# PERIPHERALS.net
KiCad netlist of a schematic drawn in Altium Designer
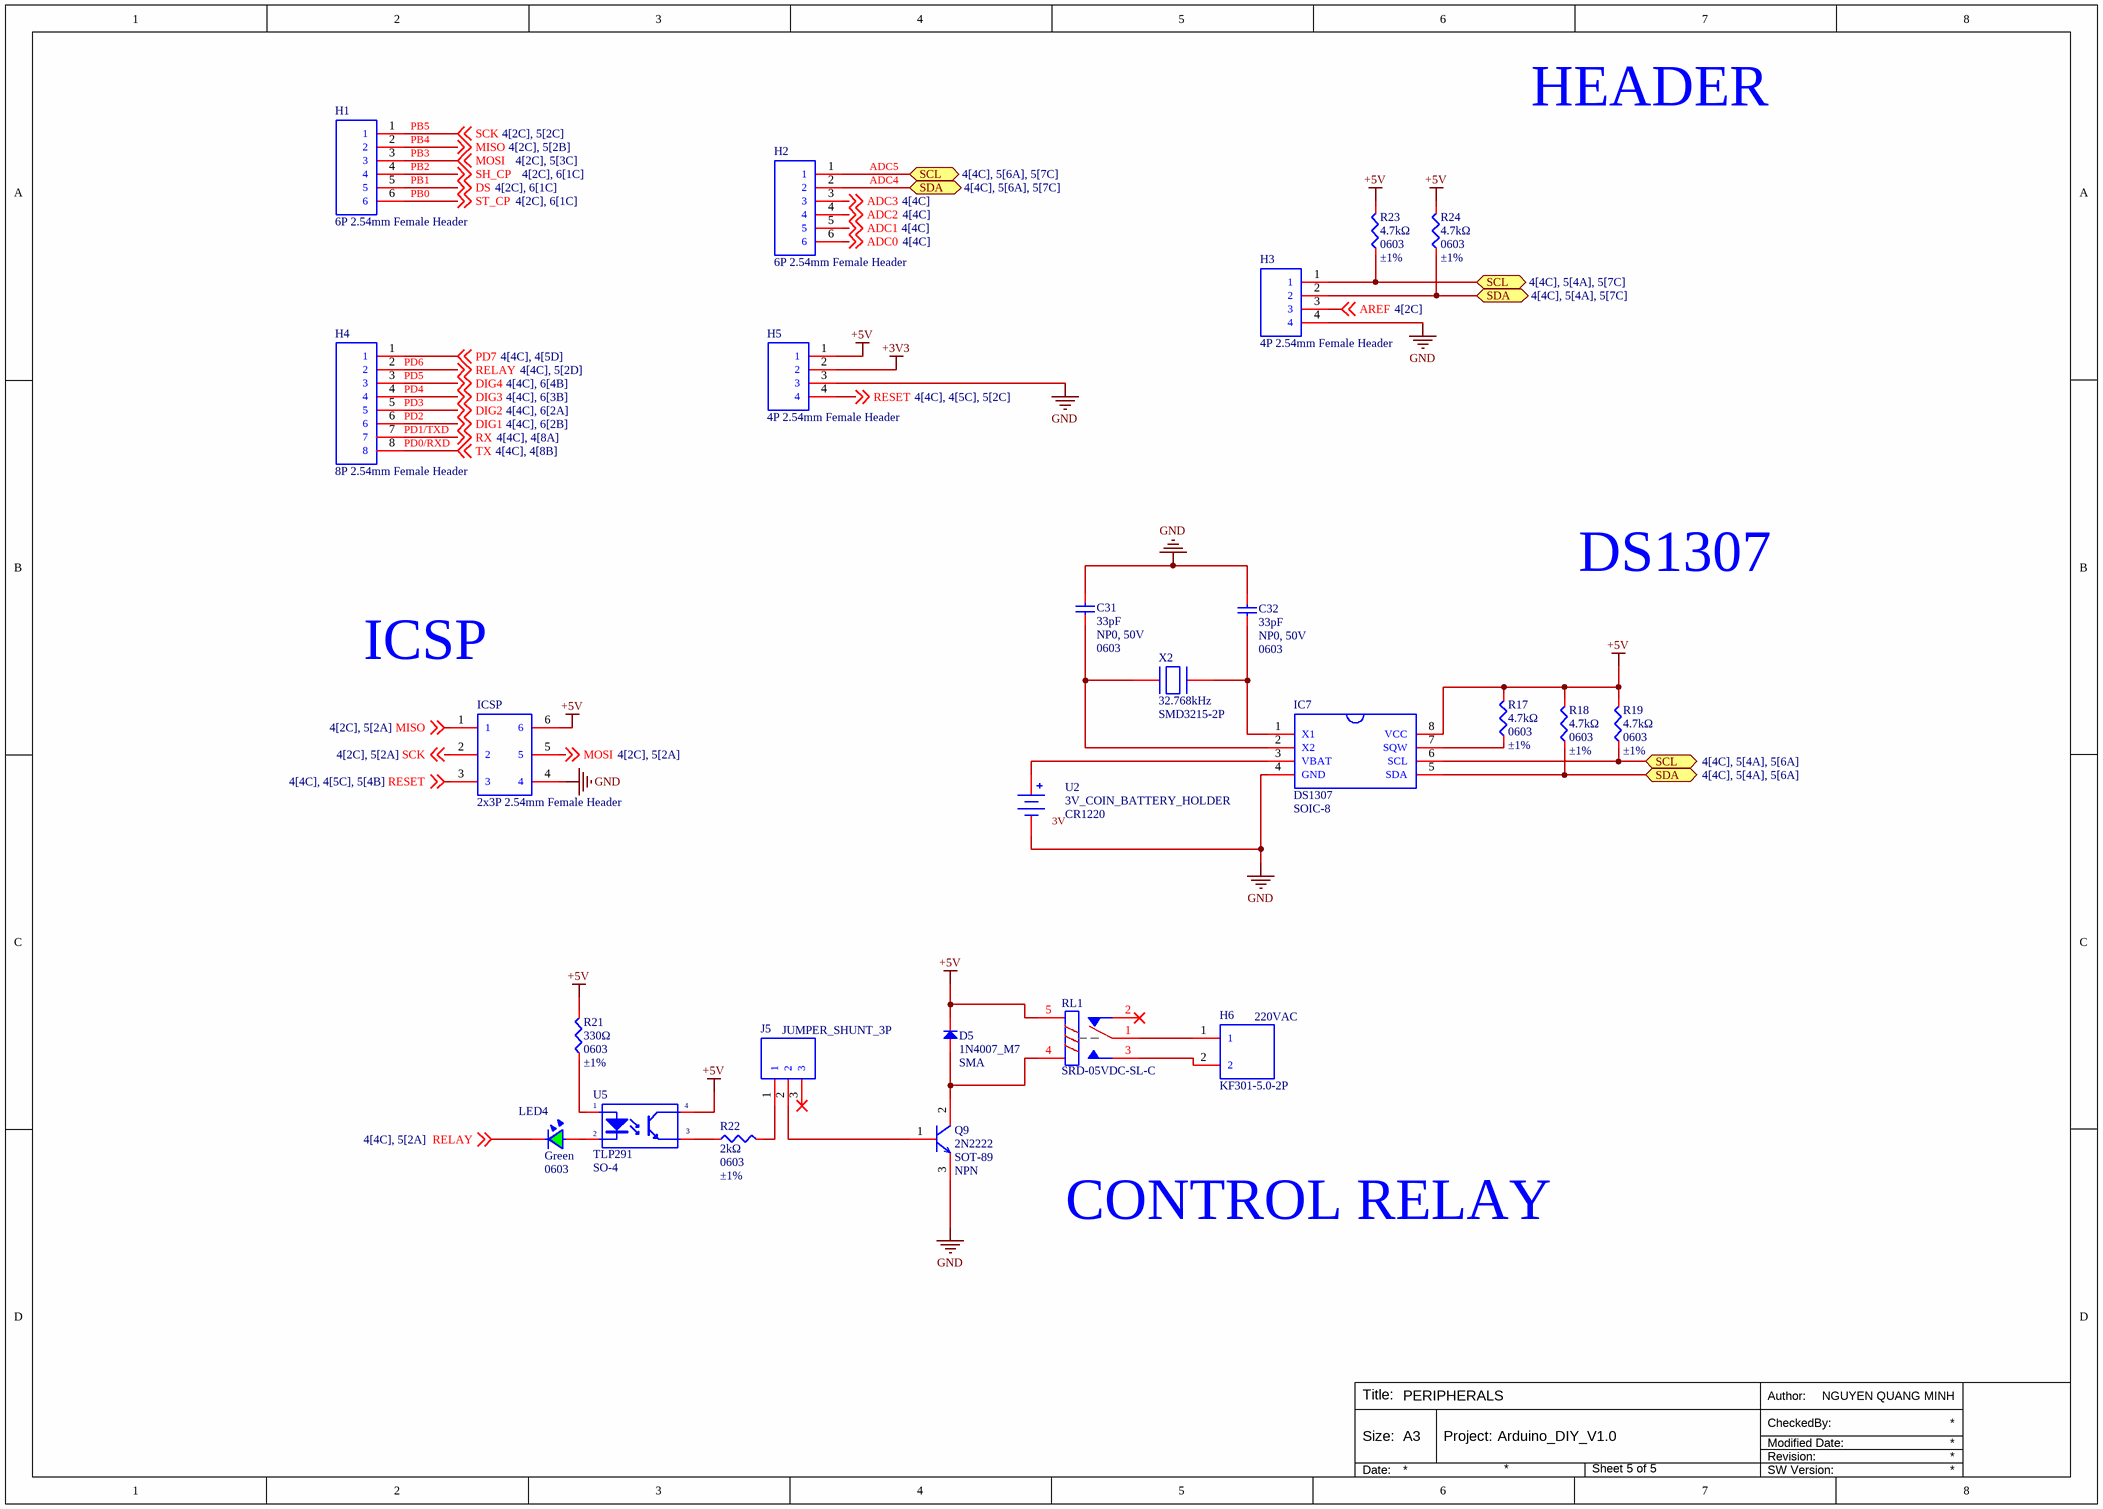
[diagram p0: PERIPHERALS.SchDoc]

(export (version "E")
  (design (tool "Eeschema 10.0.6"))
  (components
    (comp (ref "C31")
      (value "33pF")
      (footprint "C0603")
      (description "50V 33pF NP0 ±5% 0603 Multilayer Ceramic Capacitors MLCC - SMD/SMT ROHS")
      (fields
        (field (name "MANUFACTURER") "YAGEO")
        (field (name "MFR. PART") "CC0603JRNPO9BN330")
        (field (name "TEMPERATURE COEFFICIENT") "NP0, 50V")
        (field (name "PACKAGE") "0603")
      )
      (libsource (lib "Capacitor") (part "C0603_MLCC_33pF_NP0_50V"))
    )
    (comp (ref "C32")
      (value "33pF")
      (footprint "C0603")
      (description "50V 33pF NP0 ±5% 0603 Multilayer Ceramic Capacitors MLCC - SMD/SMT ROHS")
      (fields
        (field (name "MANUFACTURER") "YAGEO")
        (field (name "MFR. PART") "CC0603JRNPO9BN330")
        (field (name "TEMPERATURE COEFFICIENT") "NP0, 50V")
        (field (name "PACKAGE") "0603")
      )
      (libsource (lib "Capacitor") (part "C0603_MLCC_33pF_NP0_50V"))
    )
    (comp (ref "D5")
      (value "1N4007_M7")
      (footprint "SMA(DO-214AC)")
      (description "1A 1V@1A 1kV SMA Diodes - General Purpose ROHS")
      (fields
        (field (name "MANUFACTURER") "JSMSEMI")
        (field (name "MFR. PART") "1N4007 M7")
        (field (name "PACKAGE") "SMA")
      )
      (libsource (lib "DIODE") (part "1N4007_M7"))
    )
    (comp (ref "H1")
      (value "6P 2.54mm Female Header")
      (footprint "6P, 2,54mm, FEMALE HEADER")
      (description "2.54mm 1 6P Through Hole 1x6P Through Hole,P=2.54mm Female Headers ROHS")
      (fields
        (field (name "MANUFACTURER") "BOOMELE(Boom Precision Elec)")
        (field (name "MFR. PART") "2.54-1*6P")
      )
      (libsource (lib "HEADER") (part "6P 2.54mm Female Header"))
    )
    (comp (ref "H2")
      (value "6P 2.54mm Female Header")
      (footprint "6P, 2,54mm, FEMALE HEADER")
      (description "2.54mm 1 6P Through Hole 1x6P Through Hole,P=2.54mm Female Headers ROHS")
      (fields
        (field (name "MANUFACTURER") "BOOMELE(Boom Precision Elec)")
        (field (name "MFR. PART") "2.54-1*6P")
      )
      (libsource (lib "HEADER") (part "6P 2.54mm Female Header"))
    )
    (comp (ref "H3")
      (value "4P 2.54mm Female Header")
      (footprint "4P, 2,54mm, FEMALE HEADER")
      (fields
        (field (name "MANUFACTURER") "BOOMELE(Boom Precision Elec)")
        (field (name "MFR. PART") "2.54-1*4P")
        (field (name "LCSC PART") "C2718488")
      )
      (libsource (lib "HEADER") (part "4P 2.54mm Female Header"))
    )
    (comp (ref "H4")
      (value "8P 2.54mm Female Header")
      (footprint "8P, 2,54mm, FEMALE HEADER")
      (description "2.54mm 1 8P Through Hole 1x8P Through Hole,P=2.54mm Female Headers ROHS")
      (fields
        (field (name "MANUFACTURER") "BOOMELE(Boom Precision Elec)")
        (field (name "MFR. PART") "2.54-1*8P")
      )
      (libsource (lib "HEADER") (part "8P 2.54mm Female Header"))
    )
    (comp (ref "H5")
      (value "4P 2.54mm Female Header")
      (footprint "4P, 2,54mm, FEMALE HEADER")
      (fields
        (field (name "MANUFACTURER") "BOOMELE(Boom Precision Elec)")
        (field (name "MFR. PART") "2.54-1*4P")
        (field (name "LCSC PART") "C2718488")
      )
      (libsource (lib "HEADER") (part "4P 2.54mm Female Header"))
    )
    (comp (ref "H6")
      (value "KF301-5.0-2P")
      (footprint "CONN-TH_P5.00_KF301-5.0-2P")
      (fields
        (field (name "MANUFACTURER") "Cixi Kefa Elec")
        (field (name "LCSC PART") "C474881")
        (field (name "CONFIGURE") "220VAC")
      )
      (libsource (lib "CONNECTER") (part "KF301-5.0-2P"))
    )
    (comp (ref "IC7")
      (value "DS1307")
      (footprint "SOIC-8")
      (description "I2C SOIC-8 Real Time Clocks ROHS")
      (fields
        (field (name "MANUFACTURER") "MAXIM")
        (field (name "MFR. PART") "DS1307Z+T&R")
        (field (name "PACKAGE") "SOIC-8")
      )
      (libsource (lib "IC") (part "DS1307-SOIC8"))
    )
    (comp (ref "ICSP")
      (value "2x3P 2.54mm Female Header")
      (footprint "2x3P, 2.54mm, Female Header")
      (fields
        (field (name "MANUFACTURER") "HanElectricity")
        (field (name "MFR. PART") "2541FV-2x3P")
        (field (name "LCSC PART") "C18723054")
      )
      (libsource (lib "HEADER") (part "2x3P 2.54mm Female Header"))
    )
    (comp (ref "J5")
      (value "JUMPER_SHUNT_3P")
      (footprint "JUMPER_SHUNT_3P")
      (fields
        (field (name "MANUFACTURER") "XFCN")
        (field (name "MFR. PART") "PZ254V-11-03P")
        (field (name "LCSC PART") "C2937625")
      )
      (libsource (lib "JUMP") (part "JUMPER_SHUNT_3P"))
    )
    (comp (ref "LED4")
      (value "Green")
      (footprint "LED0603_GREEN")
      (fields
        (field (name "MANUFACTURER") "Kingbright")
        (field (name "MFR. PART") "KPT-1608LVZGCK")
        (field (name "LCSC PART") "C598356")
        (field (name "PACKAGE") "0603")
      )
      (libsource (lib "LED") (part "LED0603_Green"))
    )
    (comp (ref "Q9")
      (value "2N2222")
      (footprint "SOT-89-3L")
      (description "40V 500mW 600mA NPN SOT-89 Bipolar (BJT) ROHS")
      (fields
        (field (name "MANUFACTURER") "CBI")
        (field (name "MFR. PART") "2N2222AU")
        (field (name "PACKAGE") "SOT-89")
        (field (name "TYPE") "NPN")
      )
      (libsource (lib "BJT and FET") (part "2N2222_SOT-89"))
    )
    (comp (ref "R17")
      (value "4.7kΩ")
      (footprint "R0603")
      (description "100mW Thick Film Resistor 75V ±100ppm/℃ ±1% 4.7kΩ 0603 Chip Resistor - Surface Mount ROHS")
      (fields
        (field (name "MANUFACTURER") "YAGEO")
        (field (name "MFR. PART") "RC0603FR-074K7L")
        (field (name "PACKAGE") "0603")
        (field (name "TOLERANCE") "±1%")
      )
      (libsource (lib "Resistor") (part "R0603_4.7kΩ_±1%"))
    )
    (comp (ref "R18")
      (value "4.7kΩ")
      (footprint "R0603")
      (description "100mW Thick Film Resistor 75V ±100ppm/℃ ±1% 4.7kΩ 0603 Chip Resistor - Surface Mount ROHS")
      (fields
        (field (name "MANUFACTURER") "YAGEO")
        (field (name "MFR. PART") "RC0603FR-074K7L")
        (field (name "PACKAGE") "0603")
        (field (name "TOLERANCE") "±1%")
      )
      (libsource (lib "Resistor") (part "R0603_4.7kΩ_±1%"))
    )
    (comp (ref "R19")
      (value "4.7kΩ")
      (footprint "R0603")
      (description "100mW Thick Film Resistor 75V ±100ppm/℃ ±1% 4.7kΩ 0603 Chip Resistor - Surface Mount ROHS")
      (fields
        (field (name "MANUFACTURER") "YAGEO")
        (field (name "MFR. PART") "RC0603FR-074K7L")
        (field (name "PACKAGE") "0603")
        (field (name "TOLERANCE") "±1%")
      )
      (libsource (lib "Resistor") (part "R0603_4.7kΩ_±1%"))
    )
    (comp (ref "R21")
      (value "330Ω")
      (footprint "R0603")
      (description "100mW Thick Film Resistor 75V ±100ppm/℃ ±1% 330Ω 0603 Chip Resistor - Surface Mount ROHS")
      (fields
        (field (name "MANUFACTURER") "YAGEO")
        (field (name "MFR. PART") "RC0603FR-07330RL")
        (field (name "PACKAGE") "0603")
        (field (name "TOLERANCE") "±1%")
      )
      (libsource (lib "Resistor") (part "R0603_330Ω_±1%"))
    )
    (comp (ref "R22")
      (value "2kΩ")
      (footprint "R0603")
      (description "100mW Thick Film Resistor 75V ±100ppm/℃ ±1% 2kΩ 0603 Chip Resistor - Surface Mount ROHS")
      (fields
        (field (name "MANUFACTURER") "YAGEO")
        (field (name "MFR. PART") "RC0603FR-072KL")
        (field (name "PACKAGE") "0603")
        (field (name "TOLERANCE") "±1%")
      )
      (libsource (lib "Resistor") (part "R0603_2kΩ_±1%"))
    )
    (comp (ref "R23")
      (value "4.7kΩ")
      (footprint "R0603")
      (description "100mW Thick Film Resistor 75V ±100ppm/℃ ±1% 4.7kΩ 0603 Chip Resistor - Surface Mount ROHS")
      (fields
        (field (name "MANUFACTURER") "YAGEO")
        (field (name "MFR. PART") "RC0603FR-074K7L")
        (field (name "PACKAGE") "0603")
        (field (name "TOLERANCE") "±1%")
      )
      (libsource (lib "Resistor") (part "R0603_4.7kΩ_±1%"))
    )
    (comp (ref "R24")
      (value "4.7kΩ")
      (footprint "R0603")
      (description "100mW Thick Film Resistor 75V ±100ppm/℃ ±1% 4.7kΩ 0603 Chip Resistor - Surface Mount ROHS")
      (fields
        (field (name "MANUFACTURER") "YAGEO")
        (field (name "MFR. PART") "RC0603FR-074K7L")
        (field (name "PACKAGE") "0603")
        (field (name "TOLERANCE") "±1%")
      )
      (libsource (lib "Resistor") (part "R0603_4.7kΩ_±1%"))
    )
    (comp (ref "RL1")
      (value "SRD-05VDC-SL-C")
      (footprint "Through Hole,15.6x19.2mm")
      (description "250V@AC 5V 15A 1 Form C: 1C (SPDT-CO) Through Hole,15.6x19.2mm Power Relays ROHS")
      (fields (field (name "MANUFACTURER") "Songle Relay") (field (name "LCSC PART") "C35449"))
      (libsource (lib "RELAY") (part "SRD-05VDC-SL-C"))
    )
    (comp (ref "U2")
      (value "3V_COIN_BATTERY_HOLDER")
      (footprint "3V_COIN_BATERRY_HOLDER_CR1220")
      (description "Battery Holder -25℃~+85℃ Phosphor Bronze CR1220 SMD Button And Strip Battery Connector ROHS")
      (fields
        (field (name "MANUFACTURER") "MYOUNG")
        (field (name "LCSC PART") "C964723")
        (field (name "BATTERY TYPE") "CR1220")
      )
      (libsource (lib "PIN") (part "3V_COIN_BATTERY_HOLDER"))
    )
    (comp (ref "U5")
      (value "TLP291")
      (footprint "SO-4")
      (description "SO-4 Transistor, Photovoltaic Output Optoisolators ROHS")
      (fields
        (field (name "MANUFACTURER") "TOSHIBA")
        (field (name "MFR. PART") "TLP291(GB-TP,SE(T")
        (field (name "PACKAGE") "SO-4")
      )
      (libsource (lib "OPTO") (part "TLP291"))
    )
    (comp (ref "X2")
      (value "32.768kHz")
      (footprint "SMD3215-2P")
      (description "32.768kHz 12.5pF ±20ppm SMD3215-2P Crystals ROHS")
      (fields
        (field (name "MANUFACTURER") "NDK")
        (field (name "MFR. PART") "NX3215SA-32.768K-STD-MUA-8")
        (field (name "PACKAGE") "SMD3215-2P")
      )
      (libsource (lib "CRYSTAL") (part "Crystal_32.768Khz"))
    )
  )
  (nets
    (net (code "1") (name "+3V3") (class "Default")
      (node (ref "H5") (pin "2") (pinfunction "2_2") (pintype "passive"))
    )
    (net (code "2") (name "+5V") (class "Default")
      (node (ref "D5") (pin "1") (pinfunction "1_1") (pintype "passive"))
      (node (ref "H5") (pin "1") (pinfunction "1_1") (pintype "passive"))
      (node (ref "IC7") (pin "8") (pinfunction "VCC_8") (pintype "passive"))
      (node (ref "ICSP") (pin "6") (pinfunction "6_6") (pintype "passive"))
      (node (ref "R17") (pin "2") (pinfunction "2_2") (pintype "passive"))
      (node (ref "R18") (pin "2") (pinfunction "2_2") (pintype "passive"))
      (node (ref "R19") (pin "2") (pinfunction "2_2") (pintype "passive"))
      (node (ref "R21") (pin "2") (pinfunction "2_2") (pintype "passive"))
      (node (ref "R23") (pin "2") (pinfunction "2_2") (pintype "passive"))
      (node (ref "R24") (pin "2") (pinfunction "2_2") (pintype "passive"))
      (node (ref "RL1") (pin "5") (pinfunction "5_5") (pintype "passive"))
      (node (ref "U5") (pin "4") (pinfunction "C_4") (pintype "passive"))
    )
    (net (code "3") (name "/SCL") (class "Default")
      (node (ref "H2") (pin "1") (pinfunction "1_1") (pintype "passive"))
      (node (ref "H3") (pin "1") (pinfunction "1_1") (pintype "passive"))
      (node (ref "IC7") (pin "6") (pinfunction "SCL_6") (pintype "passive"))
      (node (ref "R19") (pin "1") (pinfunction "1_1") (pintype "passive"))
      (node (ref "R23") (pin "1") (pinfunction "1_1") (pintype "passive"))
    )
    (net (code "4") (name "/SDA") (class "Default")
      (node (ref "H2") (pin "2") (pinfunction "2_2") (pintype "passive"))
      (node (ref "H3") (pin "2") (pinfunction "2_2") (pintype "passive"))
      (node (ref "IC7") (pin "5") (pinfunction "SDA_5") (pintype "passive"))
      (node (ref "R18") (pin "1") (pinfunction "1_1") (pintype "passive"))
      (node (ref "R24") (pin "1") (pinfunction "1_1") (pintype "passive"))
    )
    (net (code "5") (name "ADC0") (class "Default")
      (node (ref "H2") (pin "6") (pinfunction "6_6") (pintype "passive"))
    )
    (net (code "6") (name "ADC1") (class "Default")
      (node (ref "H2") (pin "5") (pinfunction "5_5") (pintype "passive"))
    )
    (net (code "7") (name "ADC2") (class "Default")
      (node (ref "H2") (pin "4") (pinfunction "4_4") (pintype "passive"))
    )
    (net (code "8") (name "ADC3") (class "Default")
      (node (ref "H2") (pin "3") (pinfunction "3_3") (pintype "passive"))
    )
    (net (code "9") (name "AREF") (class "Default")
      (node (ref "H3") (pin "3") (pinfunction "3_3") (pintype "passive"))
    )
    (net (code "10") (name "DIG1") (class "Default")
      (node (ref "H4") (pin "6") (pinfunction "6_6") (pintype "passive"))
    )
    (net (code "11") (name "DIG2") (class "Default")
      (node (ref "H4") (pin "5") (pinfunction "5_5") (pintype "passive"))
    )
    (net (code "12") (name "DIG3") (class "Default")
      (node (ref "H4") (pin "4") (pinfunction "4_4") (pintype "passive"))
    )
    (net (code "13") (name "DIG4") (class "Default")
      (node (ref "H4") (pin "3") (pinfunction "3_3") (pintype "passive"))
    )
    (net (code "14") (name "DS") (class "Default")
      (node (ref "H1") (pin "5") (pinfunction "5_5") (pintype "passive"))
    )
    (net (code "15") (name "GND") (class "Default")
      (node (ref "C31") (pin "2") (pinfunction "2_2") (pintype "passive"))
      (node (ref "C32") (pin "2") (pinfunction "2_2") (pintype "passive"))
      (node (ref "H3") (pin "4") (pinfunction "4_4") (pintype "passive"))
      (node (ref "H5") (pin "3") (pinfunction "3_3") (pintype "passive"))
      (node (ref "IC7") (pin "4") (pinfunction "GND_4") (pintype "passive"))
      (node (ref "ICSP") (pin "4") (pinfunction "4_4") (pintype "passive"))
      (node (ref "Q9") (pin "3") (pinfunction "E_3") (pintype "passive"))
      (node (ref "U2") (pin "2") (pinfunction "2_2") (pintype "passive"))
    )
    (net (code "16") (name "MISO") (class "Default")
      (node (ref "H1") (pin "2") (pinfunction "2_2") (pintype "passive"))
      (node (ref "ICSP") (pin "1") (pinfunction "1_1") (pintype "passive"))
    )
    (net (code "17") (name "MOSI") (class "Default")
      (node (ref "H1") (pin "3") (pinfunction "3_3") (pintype "passive"))
      (node (ref "ICSP") (pin "5") (pinfunction "5_5") (pintype "passive"))
    )
    (net (code "18") (name "Net-(H6-Pad1)") (class "Default")
      (node (ref "H6") (pin "1") (pinfunction "1_1") (pintype "passive"))
      (node (ref "RL1") (pin "1") (pinfunction "1_1") (pintype "passive"))
    )
    (net (code "19") (name "Net-(H6-Pad2)") (class "Default")
      (node (ref "H6") (pin "2") (pinfunction "2_2") (pintype "passive"))
      (node (ref "RL1") (pin "3") (pinfunction "3_3") (pintype "passive"))
    )
    (net (code "20") (name "Net-(IC7-SQW)") (class "Default")
      (node (ref "IC7") (pin "7") (pinfunction "SQW_7") (pintype "passive"))
      (node (ref "R17") (pin "1") (pinfunction "1_1") (pintype "passive"))
    )
    (net (code "21") (name "Net-(IC7-VBAT)") (class "Default")
      (node (ref "IC7") (pin "3") (pinfunction "VBAT_3") (pintype "passive"))
      (node (ref "U2") (pin "1") (pinfunction "1_1") (pintype "passive"))
    )
    (net (code "22") (name "Net-(IC7-X1)") (class "Default")
      (node (ref "C32") (pin "1") (pinfunction "1_1") (pintype "passive"))
      (node (ref "IC7") (pin "1") (pinfunction "X1_1") (pintype "passive"))
      (node (ref "X2") (pin "1") (pinfunction "1_1") (pintype "passive"))
    )
    (net (code "23") (name "Net-(IC7-X2)") (class "Default")
      (node (ref "C31") (pin "1") (pinfunction "1_1") (pintype "passive"))
      (node (ref "IC7") (pin "2") (pinfunction "X2_2") (pintype "passive"))
      (node (ref "X2") (pin "2") (pinfunction "2_2") (pintype "passive"))
    )
    (net (code "24") (name "Net-(J5-Pad1)") (class "Default")
      (node (ref "J5") (pin "1") (pinfunction "1_1") (pintype "passive"))
      (node (ref "R22") (pin "2") (pinfunction "2_2") (pintype "passive"))
    )
    (net (code "25") (name "Net-(Q9-B)") (class "Default")
      (node (ref "J5") (pin "2") (pinfunction "2_2") (pintype "passive"))
      (node (ref "Q9") (pin "1") (pinfunction "B_1") (pintype "passive"))
    )
    (net (code "26") (name "Net-(Q9-C)") (class "Default")
      (node (ref "D5") (pin "2") (pinfunction "2_2") (pintype "passive"))
      (node (ref "Q9") (pin "2") (pinfunction "C_2") (pintype "passive"))
      (node (ref "RL1") (pin "4") (pinfunction "4_4") (pintype "passive"))
    )
    (net (code "27") (name "Net-(U5-A)") (class "Default")
      (node (ref "R21") (pin "1") (pinfunction "1_1") (pintype "passive"))
      (node (ref "U5") (pin "1") (pinfunction "A_1") (pintype "passive"))
    )
    (net (code "28") (name "Net-(U5-E)") (class "Default")
      (node (ref "R22") (pin "1") (pinfunction "1_1") (pintype "passive"))
      (node (ref "U5") (pin "3") (pinfunction "E_3") (pintype "passive"))
    )
    (net (code "29") (name "Net-(U5-K)") (class "Default")
      (node (ref "LED4") (pin "1") (pinfunction "1_1") (pintype "passive"))
      (node (ref "U5") (pin "2") (pinfunction "K_2") (pintype "passive"))
    )
    (net (code "30") (name "PD7") (class "Default")
      (node (ref "H4") (pin "1") (pinfunction "1_1") (pintype "passive"))
    )
    (net (code "31") (name "RELAY") (class "Default")
      (node (ref "H4") (pin "2") (pinfunction "2_2") (pintype "passive"))
      (node (ref "LED4") (pin "2") (pinfunction "2_2") (pintype "passive"))
    )
    (net (code "32") (name "RESET") (class "Default")
      (node (ref "H5") (pin "4") (pinfunction "4_4") (pintype "passive"))
      (node (ref "ICSP") (pin "3") (pinfunction "3_3") (pintype "passive"))
    )
    (net (code "33") (name "RX") (class "Default")
      (node (ref "H4") (pin "7") (pinfunction "7_7") (pintype "passive"))
    )
    (net (code "34") (name "SCK") (class "Default")
      (node (ref "H1") (pin "1") (pinfunction "1_1") (pintype "passive"))
      (node (ref "ICSP") (pin "2") (pinfunction "2_2") (pintype "passive"))
    )
    (net (code "35") (name "SH_CP") (class "Default")
      (node (ref "H1") (pin "4") (pinfunction "4_4") (pintype "passive"))
    )
    (net (code "36") (name "ST_CP") (class "Default")
      (node (ref "H1") (pin "6") (pinfunction "6_6") (pintype "passive"))
    )
    (net (code "37") (name "TX") (class "Default")
      (node (ref "H4") (pin "8") (pinfunction "8_8") (pintype "passive"))
    )
    (net (code "38") (name "unconnected-(J5-Pad3)") (class "Default")
      (node (ref "J5") (pin "3") (pinfunction "3_3") (pintype "passive+no_connect"))
    )
    (net (code "39") (name "unconnected-(RL1-Pad2)") (class "Default")
      (node (ref "RL1") (pin "2") (pinfunction "2_2") (pintype "passive+no_connect"))
    )
  )
)
